# untitled.net
KiCad netlist of a schematic drawn in EAGLE
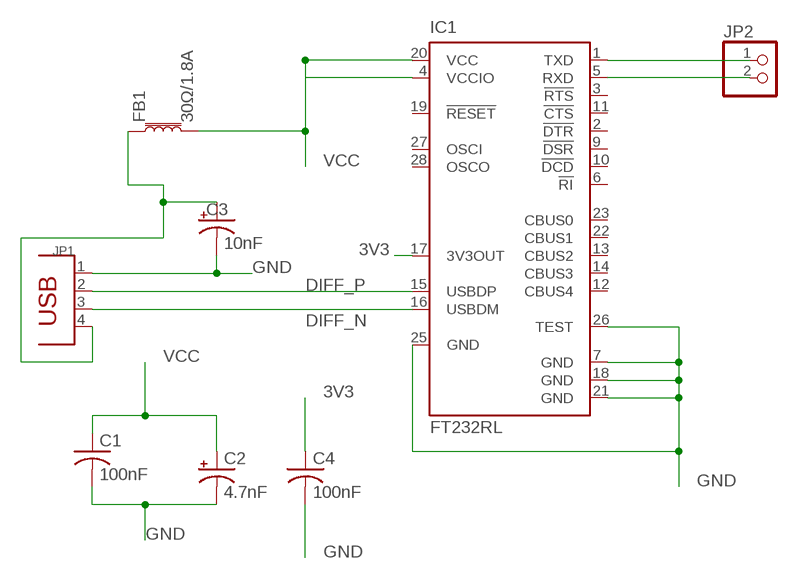
[diagram p0: schematic, sheet 1]

(export (version "E")
  (design (tool "Eeschema 10.0.6"))
  (components
    (comp (ref "C1")
      (value "100nF")
      (footprint "eagle-import:C0805")
      (libsource (lib "eagle-import") (part "C-USC0805"))
    )
    (comp (ref "C2")
      (value "4.7nF")
      (footprint "eagle-import:B45181A")
      (libsource (lib "eagle-import") (part "CPOL-USB45181A"))
    )
    (comp (ref "C3")
      (value "10nF")
      (footprint "eagle-import:B45181A")
      (libsource (lib "eagle-import") (part "CPOL-USB45181A"))
    )
    (comp (ref "C4")
      (value "100nF")
      (footprint "eagle-import:C0805")
      (libsource (lib "eagle-import") (part "C-USC0805"))
    )
    (comp (ref "FB1")
      (value "30Ω/1.8A")
      (footprint "eagle-import:0603")
      (libsource (lib "eagle-import") (part "FERRITE_BEAD-0603"))
    )
    (comp (ref "IC1")
      (value "FT232RL")
      (footprint "eagle-import:SSOP28")
      (libsource (lib "eagle-import") (part "FT232RL"))
    )
    (comp (ref "JP1")
      (value "DIP-USB-A-TYPE-FMAL(4+2P-2.0-90D)")
      (footprint "eagle-import:USB4+2P-2.0-90D")
      (libsource (lib "eagle-import") (part "DIP-USB-A-TYPE-FMAL(4+2P-2.0-90D)"))
    )
    (comp (ref "JP2")
      (value "PINHD-1X2")
      (footprint "eagle-import:1X02")
      (libsource (lib "eagle-import") (part "PINHD-1X2"))
    )
  )
  (nets
    (net (code "1") (name "/3V3") (class "Default")
      (node (ref "C4") (pin "1") (pinfunction "1_1") (pintype "passive"))
      (node (ref "IC1") (pin "17") (pinfunction "3V3OUT_17") (pintype "output"))
    )
    (net (code "2") (name "/DIFF_N") (class "Default")
      (node (ref "IC1") (pin "16") (pinfunction "USBDM_16") (pintype "bidirectional"))
      (node (ref "JP1") (pin "3") (pinfunction "3_3") (pintype "bidirectional"))
    )
    (net (code "3") (name "/DIFF_P") (class "Default")
      (node (ref "IC1") (pin "15") (pinfunction "USBDP_15") (pintype "bidirectional"))
      (node (ref "JP1") (pin "2") (pinfunction "2_2") (pintype "bidirectional"))
    )
    (net (code "4") (name "/GND") (class "Default")
      (node (ref "C1") (pin "2") (pinfunction "2_2") (pintype "passive"))
      (node (ref "C2") (pin "-") (pinfunction "-_-") (pintype "passive"))
      (node (ref "C3") (pin "-") (pinfunction "-_-") (pintype "passive"))
      (node (ref "C4") (pin "2") (pinfunction "2_2") (pintype "passive"))
      (node (ref "IC1") (pin "18") (pinfunction "GND_18") (pintype "power_in"))
      (node (ref "IC1") (pin "21") (pinfunction "GND_21") (pintype "power_in"))
      (node (ref "IC1") (pin "25") (pinfunction "GND_25") (pintype "power_in"))
      (node (ref "IC1") (pin "26") (pinfunction "TEST_26") (pintype "input"))
      (node (ref "IC1") (pin "7") (pinfunction "GND_7") (pintype "power_in"))
      (node (ref "JP1") (pin "1") (pinfunction "1_1") (pintype "bidirectional"))
    )
    (net (code "5") (name "/VCC") (class "Default")
      (node (ref "C1") (pin "1") (pinfunction "1_1") (pintype "passive"))
      (node (ref "C2") (pin "+") (pinfunction "+_+") (pintype "passive"))
      (node (ref "FB1") (pin "2") (pinfunction "2_2") (pintype "passive"))
      (node (ref "IC1") (pin "20") (pinfunction "VCC_20") (pintype "power_in"))
      (node (ref "IC1") (pin "4") (pinfunction "VCCIO_4") (pintype "power_in"))
    )
    (net (code "6") (name "Net-(C3-Pad+)") (class "Default")
      (node (ref "C3") (pin "+") (pinfunction "+_+") (pintype "passive"))
      (node (ref "FB1") (pin "1") (pinfunction "1_1") (pintype "passive"))
      (node (ref "JP1") (pin "4") (pinfunction "4_4") (pintype "bidirectional"))
    )
    (net (code "7") (name "Net-(IC1-RXD)") (class "Default")
      (node (ref "IC1") (pin "5") (pinfunction "RXD_5") (pintype "input"))
      (node (ref "JP2") (pin "2") (pinfunction "2_2") (pintype "passive"))
    )
    (net (code "8") (name "Net-(IC1-TXD)") (class "Default")
      (node (ref "IC1") (pin "1") (pinfunction "TXD_1") (pintype "output"))
      (node (ref "JP2") (pin "1") (pinfunction "1_1") (pintype "passive"))
    )
    (net (code "9") (name "unconnected-(IC1-CBUS0-Pad23)") (class "Default")
      (node (ref "IC1") (pin "23") (pinfunction "CBUS0_23") (pintype "bidirectional"))
    )
    (net (code "10") (name "unconnected-(IC1-CBUS1-Pad22)") (class "Default")
      (node (ref "IC1") (pin "22") (pinfunction "CBUS1_22") (pintype "bidirectional"))
    )
    (net (code "11") (name "unconnected-(IC1-CBUS2-Pad13)") (class "Default")
      (node (ref "IC1") (pin "13") (pinfunction "CBUS2_13") (pintype "bidirectional"))
    )
    (net (code "12") (name "unconnected-(IC1-CBUS3-Pad14)") (class "Default")
      (node (ref "IC1") (pin "14") (pinfunction "CBUS3_14") (pintype "bidirectional"))
    )
    (net (code "13") (name "unconnected-(IC1-CBUS4-Pad12)") (class "Default")
      (node (ref "IC1") (pin "12") (pinfunction "CBUS4_12") (pintype "bidirectional"))
    )
    (net (code "14") (name "unconnected-(IC1-OSCI-Pad27)") (class "Default")
      (node (ref "IC1") (pin "27") (pinfunction "OSCI_27") (pintype "input"))
    )
    (net (code "15") (name "unconnected-(IC1-OSCO-Pad28)") (class "Default")
      (node (ref "IC1") (pin "28") (pinfunction "OSCO_28") (pintype "output"))
    )
    (net (code "16") (name "unconnected-(IC1-~{CTS}-Pad11)") (class "Default")
      (node (ref "IC1") (pin "11") (pinfunction "~{CTS}_11") (pintype "input"))
    )
    (net (code "17") (name "unconnected-(IC1-~{DCD}-Pad10)") (class "Default")
      (node (ref "IC1") (pin "10") (pinfunction "~{DCD}_10") (pintype "input"))
    )
    (net (code "18") (name "unconnected-(IC1-~{DSR}-Pad9)") (class "Default")
      (node (ref "IC1") (pin "9") (pinfunction "~{DSR}_9") (pintype "input"))
    )
    (net (code "19") (name "unconnected-(IC1-~{DTR}-Pad2)") (class "Default")
      (node (ref "IC1") (pin "2") (pinfunction "~{DTR}_2") (pintype "output"))
    )
    (net (code "20") (name "unconnected-(IC1-~{RESET}-Pad19)") (class "Default")
      (node (ref "IC1") (pin "19") (pinfunction "~{RESET}_19") (pintype "input"))
    )
    (net (code "21") (name "unconnected-(IC1-~{RI}-Pad6)") (class "Default")
      (node (ref "IC1") (pin "6") (pinfunction "~{RI}_6") (pintype "input"))
    )
    (net (code "22") (name "unconnected-(IC1-~{RTS}-Pad3)") (class "Default")
      (node (ref "IC1") (pin "3") (pinfunction "~{RTS}_3") (pintype "output"))
    )
  )
)
